# QS30-MCU.net
KiCad netlist of a schematic drawn in Altium Designer
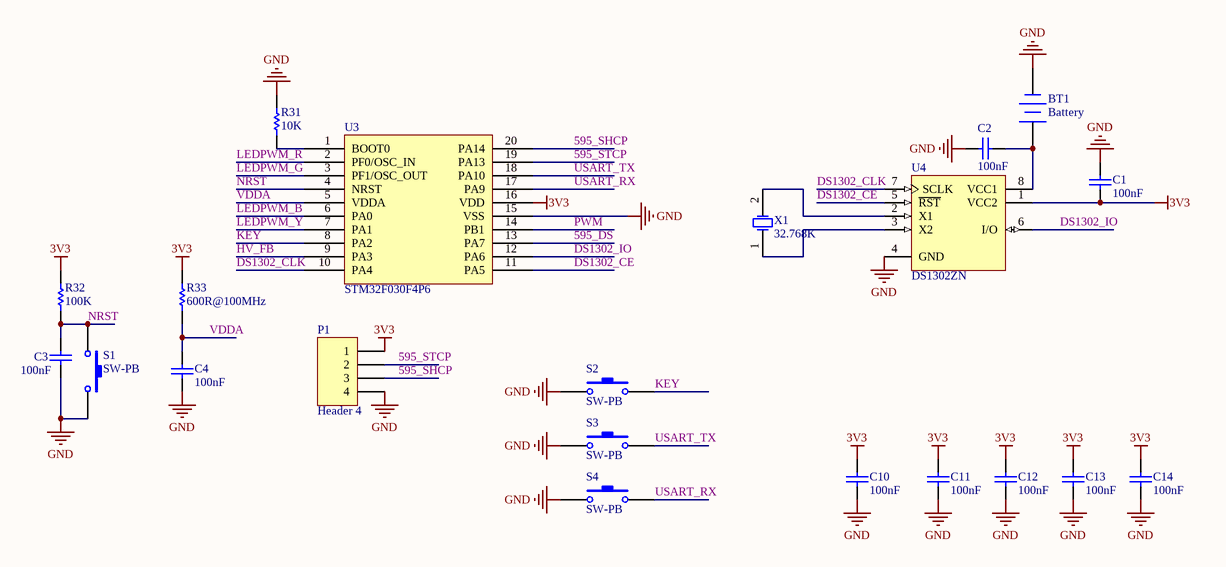
[diagram p0: QS30-MCU.SchDoc]

(export (version "E")
  (design (tool "Eeschema 10.0.6"))
  (components
    (comp (ref "BT1")
      (value "Battery")
      (footprint "BAT")
      (description "Multicell Battery")
      (fields (field (name "PUBLISHER") "Altium Limited"))
      (libsource (lib "Miscellaneous Devices") (part "Battery"))
    )
    (comp (ref "C1")
      (value "100nF")
      (footprint "6-0805_N")
      (description "Capacitor")
      (fields (field (name "Comment") "Cap") (field (name "PUBLISHER") "Altium Limited"))
      (libsource (lib "Miscellaneous Devices") (part "Cap"))
    )
    (comp (ref "C2")
      (value "100nF")
      (footprint "6-0805_N")
      (description "Capacitor")
      (fields (field (name "Comment") "Cap") (field (name "PUBLISHER") "Altium Limited"))
      (libsource (lib "Miscellaneous Devices") (part "Cap"))
    )
    (comp (ref "C3")
      (value "100nF")
      (footprint "6-0805_N")
      (description "Capacitor")
      (fields (field (name "PUBLISHER") "Altium Limited"))
      (libsource (lib "Miscellaneous Devices") (part "CAP"))
    )
    (comp (ref "C4")
      (value "100nF")
      (footprint "6-0805_N")
      (description "Capacitor")
      (fields (field (name "Comment") "Cap") (field (name "PUBLISHER") "Altium Limited"))
      (libsource (lib "Miscellaneous Devices") (part "Cap"))
    )
    (comp (ref "C10")
      (value "100nF")
      (footprint "C1210")
      (description "Capacitor")
      (fields (field (name "Comment") "Cap") (field (name "PUBLISHER") "Altium Limited"))
      (libsource (lib "Miscellaneous Devices") (part "Cap"))
    )
    (comp (ref "C11")
      (value "100nF")
      (footprint "6-0805_N")
      (description "Capacitor")
      (fields (field (name "Comment") "Cap") (field (name "PUBLISHER") "Altium Limited"))
      (libsource (lib "Miscellaneous Devices") (part "Cap"))
    )
    (comp (ref "C12")
      (value "100nF")
      (footprint "6-0805_N")
      (description "Capacitor")
      (fields (field (name "Comment") "Cap") (field (name "PUBLISHER") "Altium Limited"))
      (libsource (lib "Miscellaneous Devices") (part "Cap"))
    )
    (comp (ref "C13")
      (value "100nF")
      (footprint "6-0805_N")
      (description "Capacitor")
      (fields (field (name "Comment") "Cap") (field (name "PUBLISHER") "Altium Limited"))
      (libsource (lib "Miscellaneous Devices") (part "Cap"))
    )
    (comp (ref "C14")
      (value "100nF")
      (footprint "6-0805_N")
      (description "Capacitor")
      (fields (field (name "Comment") "Cap") (field (name "PUBLISHER") "Altium Limited"))
      (libsource (lib "Miscellaneous Devices") (part "Cap"))
    )
    (comp (ref "P1")
      (value "Header 4")
      (footprint "SWD_DOWNLOAD")
      (description "Header, 4-Pin")
      (fields (field (name "PUBLISHER") "Altium Limited"))
      (libsource (lib "Miscellaneous Connectors") (part "Header 4"))
    )
    (comp (ref "R31")
      (value "10K")
      (footprint "1608[0603]")
      (description "Resistor")
      (fields (field (name "Comment") "Res1") (field (name "PUBLISHER") "Altium Limited"))
      (libsource (lib "Miscellaneous Devices") (part "Res1"))
    )
    (comp (ref "R32")
      (value "100K")
      (footprint "6-0805_N")
      (description "Resistor")
      (fields (field (name "PUBLISHER") "Altium Limited"))
      (libsource (lib "Miscellaneous Devices") (part "res1"))
    )
    (comp (ref "R33")
      (value "600R@100MHz")
      (footprint "6-0805_N")
      (description "Resistor")
      (fields (field (name "PUBLISHER") "Altium Limited"))
      (libsource (lib "Miscellaneous Devices") (part "Res1"))
    )
    (comp (ref "S1")
      (value "SW-PB")
      (footprint "aj3X6")
      (description "Switch")
      (fields (field (name "PUBLISHER") "Altium Limited"))
      (libsource (lib "Miscellaneous Devices") (part "SW-PB"))
    )
    (comp (ref "S2")
      (value "SW-PB")
      (footprint "aj3X6")
      (description "Switch")
      (fields (field (name "PUBLISHER") "Altium Limited"))
      (libsource (lib "Miscellaneous Devices") (part "SW-PB"))
    )
    (comp (ref "S3")
      (value "SW-PB")
      (footprint "aj3X6")
      (description "Switch")
      (fields (field (name "PUBLISHER") "Altium Limited"))
      (libsource (lib "Miscellaneous Devices") (part "SW-PB"))
    )
    (comp (ref "S4")
      (value "SW-PB")
      (footprint "aj3X6")
      (description "Switch")
      (fields (field (name "PUBLISHER") "Altium Limited"))
      (libsource (lib "Miscellaneous Devices") (part "SW-PB"))
    )
    (comp (ref "U3")
      (value "STM32F030F4P6")
      (footprint "TSSOP20_N")
      (libsource (lib "常用封装库") (part "STM32F030F4P6"))
    )
    (comp (ref "U4")
      (value "DS1302ZN")
      (footprint "SOIC8N_N")
      (description "Trickle Charge Timekeeping Chip")
      (fields (field (name "PUBLISHER") "Altium Limited"))
      (libsource (lib "Dallas Peripheral Real Time Clock") (part "DS1302ZN"))
    )
    (comp (ref "X1")
      (value "32.768K")
      (footprint "MC306")
      (description "Crystal Oscillator")
      (fields (field (name "PUBLISHER") "Altium Limited"))
      (libsource (lib "Miscellaneous Devices") (part "XTAL"))
    )
  )
  (nets
    (net (code "1") (name "/595_DS") (class "Default")
      (node (ref "U3") (pin "13") (pinfunction "PA7_13") (pintype "passive"))
    )
    (net (code "2") (name "/595_SHCP") (class "Default")
      (node (ref "P1") (pin "3") (pinfunction "3_3") (pintype "passive"))
      (node (ref "U3") (pin "20") (pinfunction "PA14_20") (pintype "passive"))
    )
    (net (code "3") (name "/595_STCP") (class "Default")
      (node (ref "P1") (pin "2") (pinfunction "2_2") (pintype "passive"))
      (node (ref "U3") (pin "19") (pinfunction "PA13_19") (pintype "passive"))
    )
    (net (code "4") (name "/DS1302_CE") (class "Default")
      (node (ref "U3") (pin "11") (pinfunction "PA5_11") (pintype "passive"))
      (node (ref "U4") (pin "5") (pinfunction "~{RST}_5") (pintype "input"))
    )
    (net (code "5") (name "/DS1302_CLK") (class "Default")
      (node (ref "U3") (pin "10") (pinfunction "PA4_10") (pintype "passive"))
      (node (ref "U4") (pin "7") (pinfunction "SCLK_7") (pintype "input"))
    )
    (net (code "6") (name "/DS1302_IO") (class "Default")
      (node (ref "U3") (pin "12") (pinfunction "PA6_12") (pintype "passive"))
      (node (ref "U4") (pin "6") (pinfunction "I/O_6") (pintype "bidirectional"))
    )
    (net (code "7") (name "/HV_FB") (class "Default")
      (node (ref "U3") (pin "9") (pinfunction "PA3_9") (pintype "passive"))
    )
    (net (code "8") (name "/KEY") (class "Default")
      (node (ref "S2") (pin "2") (pinfunction "2_2") (pintype "passive"))
      (node (ref "U3") (pin "8") (pinfunction "PA2_8") (pintype "passive"))
    )
    (net (code "9") (name "/LEDPWM_B") (class "Default")
      (node (ref "U3") (pin "6") (pinfunction "PA0_6") (pintype "passive"))
    )
    (net (code "10") (name "/LEDPWM_G") (class "Default")
      (node (ref "U3") (pin "3") (pinfunction "PF1/OSC_OUT_3") (pintype "passive"))
    )
    (net (code "11") (name "/LEDPWM_R") (class "Default")
      (node (ref "U3") (pin "2") (pinfunction "PF0/OSC_IN_2") (pintype "passive"))
    )
    (net (code "12") (name "/LEDPWM_Y") (class "Default")
      (node (ref "U3") (pin "7") (pinfunction "PA1_7") (pintype "passive"))
    )
    (net (code "13") (name "/NRST") (class "Default")
      (node (ref "C3") (pin "2") (pinfunction "2_2") (pintype "passive"))
      (node (ref "R32") (pin "1") (pinfunction "1_1") (pintype "passive"))
      (node (ref "S1") (pin "1") (pinfunction "1_1") (pintype "passive"))
      (node (ref "U3") (pin "4") (pinfunction "NRST_4") (pintype "passive"))
    )
    (net (code "14") (name "/PWM") (class "Default")
      (node (ref "U3") (pin "14") (pinfunction "PB1_14") (pintype "passive"))
    )
    (net (code "15") (name "/USART_RX") (class "Default")
      (node (ref "S4") (pin "2") (pinfunction "2_2") (pintype "passive"))
      (node (ref "U3") (pin "17") (pinfunction "PA9_17") (pintype "passive"))
    )
    (net (code "16") (name "/USART_TX") (class "Default")
      (node (ref "S3") (pin "2") (pinfunction "2_2") (pintype "passive"))
      (node (ref "U3") (pin "18") (pinfunction "PA10_18") (pintype "passive"))
    )
    (net (code "17") (name "/VDDA") (class "Default")
      (node (ref "C4") (pin "2") (pinfunction "2_2") (pintype "passive"))
      (node (ref "R33") (pin "2") (pinfunction "2_2") (pintype "passive"))
      (node (ref "U3") (pin "5") (pinfunction "VDDA_5") (pintype "passive"))
    )
    (net (code "18") (name "3V3") (class "Default")
      (node (ref "C1") (pin "1") (pinfunction "1_1") (pintype "passive"))
      (node (ref "C10") (pin "2") (pinfunction "2_2") (pintype "passive"))
      (node (ref "C11") (pin "2") (pinfunction "2_2") (pintype "passive"))
      (node (ref "C12") (pin "2") (pinfunction "2_2") (pintype "passive"))
      (node (ref "C13") (pin "2") (pinfunction "2_2") (pintype "passive"))
      (node (ref "C14") (pin "2") (pinfunction "2_2") (pintype "passive"))
      (node (ref "P1") (pin "1") (pinfunction "1_1") (pintype "passive"))
      (node (ref "R32") (pin "2") (pinfunction "2_2") (pintype "passive"))
      (node (ref "R33") (pin "1") (pinfunction "1_1") (pintype "passive"))
      (node (ref "U3") (pin "16") (pinfunction "VDD_16") (pintype "passive"))
      (node (ref "U4") (pin "1") (pinfunction "VCC2_1") (pintype "power_in"))
    )
    (net (code "19") (name "GND") (class "Default")
      (node (ref "BT1") (pin "2") (pinfunction "-_2") (pintype "passive"))
      (node (ref "C1") (pin "2") (pinfunction "2_2") (pintype "passive"))
      (node (ref "C10") (pin "1") (pinfunction "1_1") (pintype "passive"))
      (node (ref "C11") (pin "1") (pinfunction "1_1") (pintype "passive"))
      (node (ref "C12") (pin "1") (pinfunction "1_1") (pintype "passive"))
      (node (ref "C13") (pin "1") (pinfunction "1_1") (pintype "passive"))
      (node (ref "C14") (pin "1") (pinfunction "1_1") (pintype "passive"))
      (node (ref "C2") (pin "2") (pinfunction "2_2") (pintype "passive"))
      (node (ref "C3") (pin "1") (pinfunction "1_1") (pintype "passive"))
      (node (ref "C4") (pin "1") (pinfunction "1_1") (pintype "passive"))
      (node (ref "P1") (pin "4") (pinfunction "4_4") (pintype "passive"))
      (node (ref "R31") (pin "2") (pinfunction "2_2") (pintype "passive"))
      (node (ref "S1") (pin "2") (pinfunction "2_2") (pintype "passive"))
      (node (ref "S2") (pin "1") (pinfunction "1_1") (pintype "passive"))
      (node (ref "S3") (pin "1") (pinfunction "1_1") (pintype "passive"))
      (node (ref "S4") (pin "1") (pinfunction "1_1") (pintype "passive"))
      (node (ref "U3") (pin "15") (pinfunction "VSS_15") (pintype "passive"))
      (node (ref "U4") (pin "4") (pinfunction "GND_4") (pintype "power_in"))
    )
    (net (code "20") (name "Net-(BT1-+)") (class "Default")
      (node (ref "BT1") (pin "1") (pinfunction "+_1") (pintype "passive"))
      (node (ref "C2") (pin "1") (pinfunction "1_1") (pintype "passive"))
      (node (ref "U4") (pin "8") (pinfunction "VCC1_8") (pintype "power_in"))
    )
    (net (code "21") (name "Net-(U3-BOOT0)") (class "Default")
      (node (ref "R31") (pin "1") (pinfunction "1_1") (pintype "passive"))
      (node (ref "U3") (pin "1") (pinfunction "BOOT0_1") (pintype "passive"))
    )
    (net (code "22") (name "Net-(U4-X1)") (class "Default")
      (node (ref "U4") (pin "2") (pinfunction "X1_2") (pintype "input"))
      (node (ref "X1") (pin "2") (pinfunction "OSC2_2") (pintype "passive"))
    )
    (net (code "23") (name "Net-(U4-X2)") (class "Default")
      (node (ref "U4") (pin "3") (pinfunction "X2_3") (pintype "input"))
      (node (ref "X1") (pin "1") (pinfunction "OSC1_1") (pintype "passive"))
    )
  )
)
